# smart_water_meter.net
KiCad netlist of a schematic drawn in EasyEDA Pro
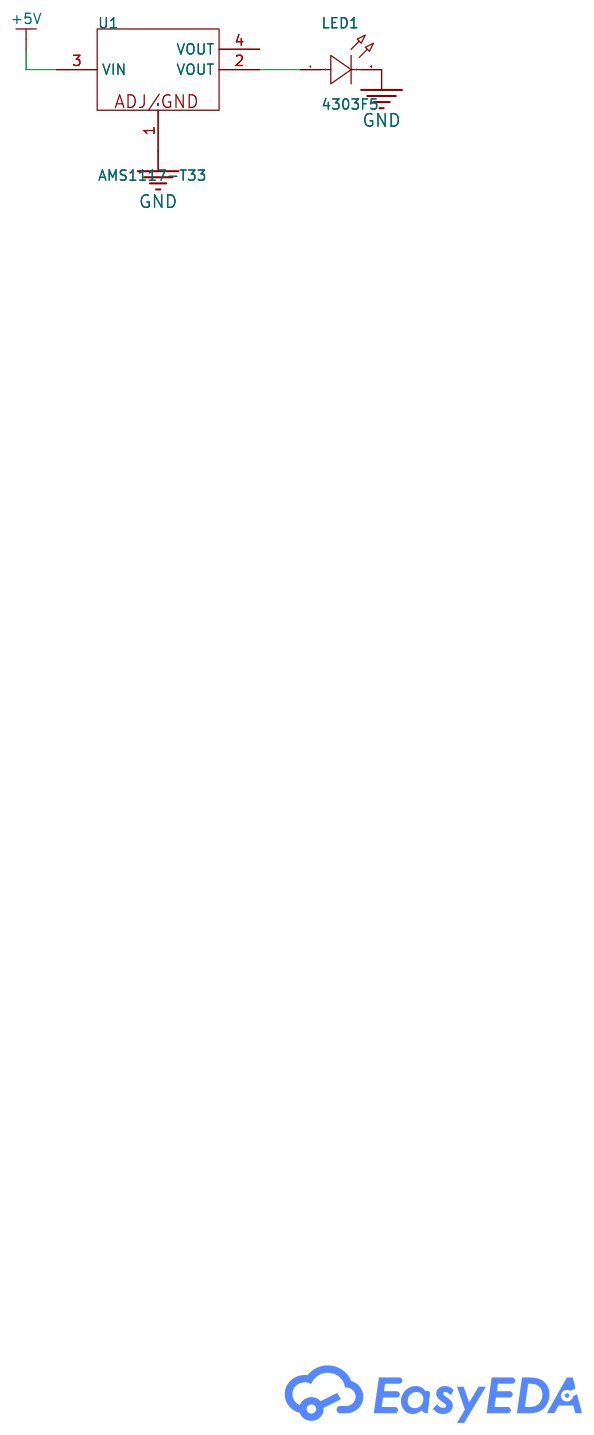
[diagram p0: schematic sheet]

(export (version "E")
  (design (tool "Eeschema 10.0.6"))
  (components
    (comp (ref "LED1")
      (value "4303F5")
      (footprint "easyedapro:LED-TH_BD3.3-P2.50-RD")
      (description "Lamp Holder Type:3mm round bulb")
      (fields (field (name "Manufacturer") "VCC"))
      (libsource (lib "easyedapro") (part "4303F5"))
    )
    (comp (ref "U1")
      (value "AMS1117-T33")
      (footprint "easyedapro:SOT-223-3_L6.5-W3.4-P2.30-LS7.0-BR")
      (fields (field (name "Manufacturer") "UNI-SEMIC(宇力半导体)"))
      (libsource (lib "easyedapro") (part "AMS1117_C400139"))
    )
  )
  (nets
    (net (code "1") (name "+5V") (class "Default")
      (node (ref "U1") (pin "3") (pinfunction "VIN_3") (pintype "unspecified"))
    )
    (net (code "2") (name "GND") (class "Default")
      (node (ref "LED1") (pin "2") (pinfunction "K_2") (pintype "unspecified"))
      (node (ref "U1") (pin "1") (pinfunction "ADJ/GND_1") (pintype "unspecified"))
    )
    (net (code "3") (name "Net-(LED1-A)") (class "Default")
      (node (ref "LED1") (pin "1") (pinfunction "A_1") (pintype "unspecified"))
      (node (ref "U1") (pin "2") (pinfunction "VOUT_2") (pintype "unspecified"))
    )
    (net (code "4") (name "unconnected-(U1-VOUT-Pad4)") (class "Default")
      (node (ref "U1") (pin "4") (pinfunction "VOUT_4") (pintype "unspecified"))
    )
  )
)
